# 10M_PPS_OUT.net
KiCad netlist of a schematic drawn in Altium Designer
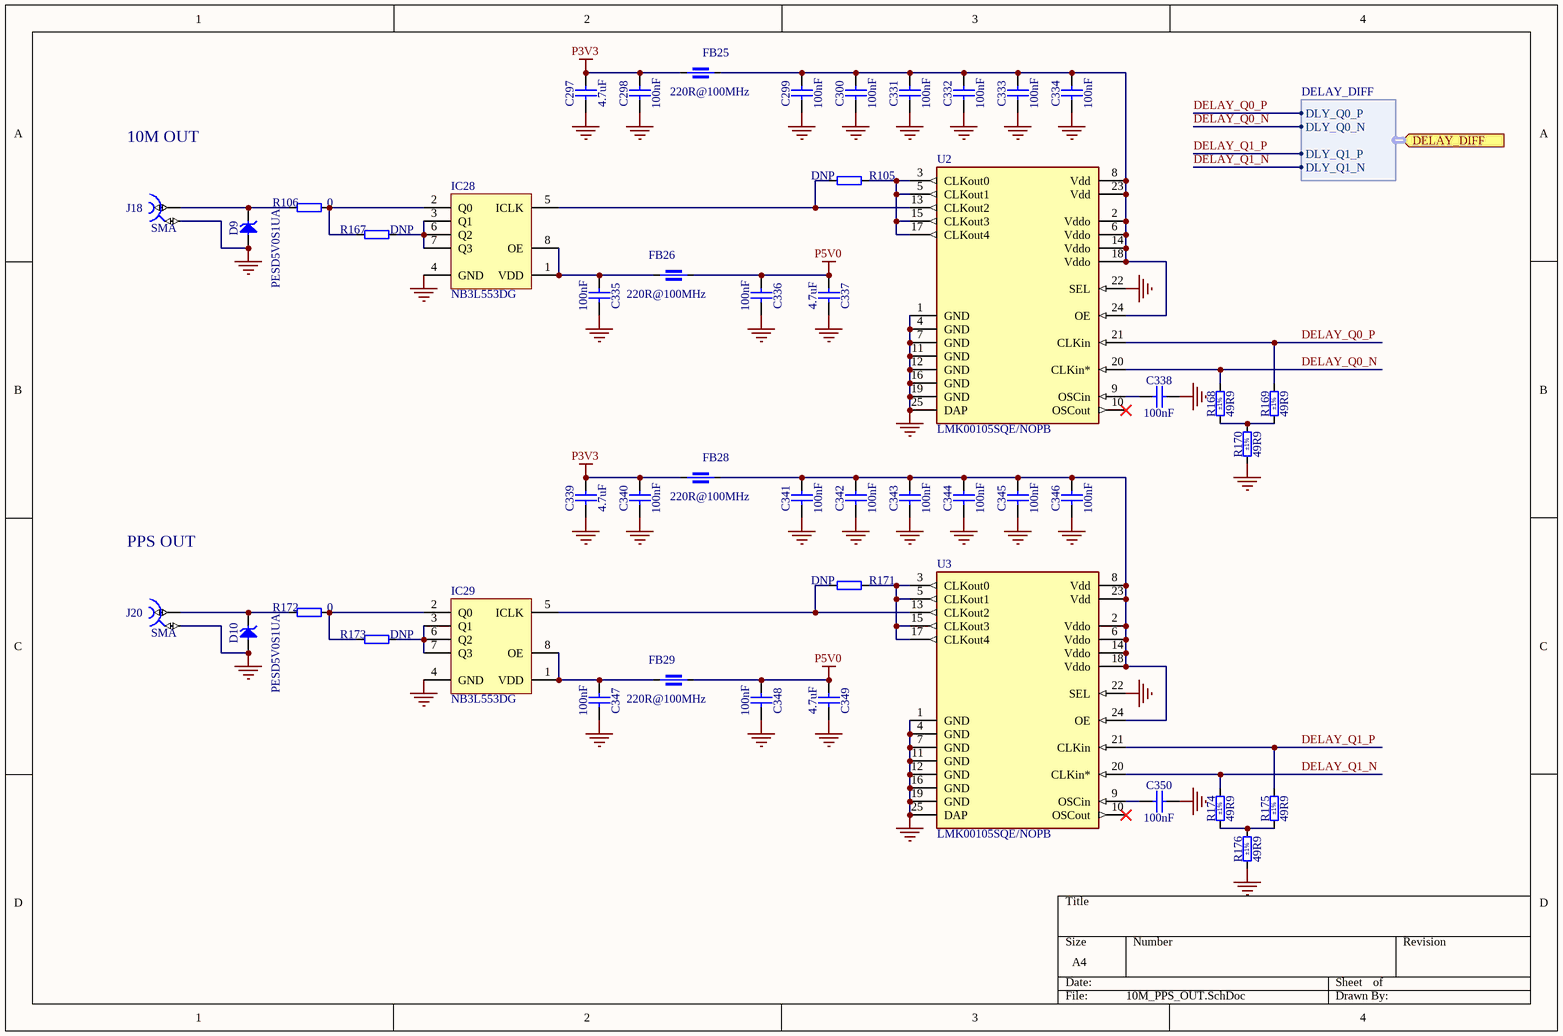
[diagram p0: 10M_PPS_OUT.SchDoc]

(export (version "E")
  (design (tool "Eeschema 10.0.6"))
  (components
    (comp (ref "C297")
      (value "4.7uF")
      (footprint "CAPC1005X55N")
      (description "Non-polarised capacitor")
      (fields
        (field (name "PART NUMBER") "CC0402_4.7UF_6.3V_20%_X5R")
        (field (name "VOLTAGE") "6.3V")
        (field (name "AUTHOR") "CERN DEM JLC")
      )
      (libsource (lib "Capacitors") (part "Capacitor - non polarized"))
    )
    (comp (ref "C298")
      (value "100nF")
      (footprint "CAPC0603X33N")
      (description "Non-polarised capacitor")
      (fields
        (field (name "PART NUMBER") "CC0201_100NF_6.3V_10%_X5R")
        (field (name "VOLTAGE") "6.3V")
        (field (name "AUTHOR") "CERN DEM JLC")
      )
      (libsource (lib "Capacitors") (part "Capacitor - non polarized"))
    )
    (comp (ref "C299")
      (value "100nF")
      (footprint "CAPC0603X33N")
      (description "Non-polarised capacitor")
      (fields
        (field (name "PART NUMBER") "CC0201_100NF_6.3V_10%_X5R")
        (field (name "VOLTAGE") "6.3V")
        (field (name "AUTHOR") "CERN DEM JLC")
      )
      (libsource (lib "Capacitors") (part "Capacitor - non polarized"))
    )
    (comp (ref "C300")
      (value "100nF")
      (footprint "CAPC0603X33N")
      (description "Non-polarised capacitor")
      (fields
        (field (name "PART NUMBER") "CC0201_100NF_6.3V_10%_X5R")
        (field (name "VOLTAGE") "6.3V")
        (field (name "AUTHOR") "CERN DEM JLC")
      )
      (libsource (lib "Capacitors") (part "Capacitor - non polarized"))
    )
    (comp (ref "C331")
      (value "100nF")
      (footprint "CAPC0603X33N")
      (description "Non-polarised capacitor")
      (fields
        (field (name "PART NUMBER") "CC0201_100NF_6.3V_10%_X5R")
        (field (name "VOLTAGE") "6.3V")
        (field (name "AUTHOR") "CERN DEM JLC")
      )
      (libsource (lib "Capacitors") (part "Capacitor - non polarized"))
    )
    (comp (ref "C332")
      (value "100nF")
      (footprint "CAPC0603X33N")
      (description "Non-polarised capacitor")
      (fields
        (field (name "PART NUMBER") "CC0201_100NF_6.3V_10%_X5R")
        (field (name "VOLTAGE") "6.3V")
        (field (name "AUTHOR") "CERN DEM JLC")
      )
      (libsource (lib "Capacitors") (part "Capacitor - non polarized"))
    )
    (comp (ref "C333")
      (value "100nF")
      (footprint "CAPC0603X33N")
      (description "Non-polarised capacitor")
      (fields
        (field (name "PART NUMBER") "CC0201_100NF_6.3V_10%_X5R")
        (field (name "VOLTAGE") "6.3V")
        (field (name "AUTHOR") "CERN DEM JLC")
      )
      (libsource (lib "Capacitors") (part "Capacitor - non polarized"))
    )
    (comp (ref "C334")
      (value "100nF")
      (footprint "CAPC0603X33N")
      (description "Non-polarised capacitor")
      (fields
        (field (name "PART NUMBER") "CC0201_100NF_6.3V_10%_X5R")
        (field (name "VOLTAGE") "6.3V")
        (field (name "AUTHOR") "CERN DEM JLC")
      )
      (libsource (lib "Capacitors") (part "Capacitor - non polarized"))
    )
    (comp (ref "C335")
      (value "100nF")
      (footprint "CAPC0603X33N")
      (description "Non-polarised capacitor")
      (fields
        (field (name "PART NUMBER") "CC0201_100NF_6.3V_10%_X5R")
        (field (name "VOLTAGE") "6.3V")
        (field (name "AUTHOR") "CERN DEM JLC")
      )
      (libsource (lib "Capacitors") (part "Capacitor - non polarized"))
    )
    (comp (ref "C336")
      (value "100nF")
      (footprint "CAPC0603X33N")
      (description "Non-polarised capacitor")
      (fields
        (field (name "PART NUMBER") "CC0201_100NF_6.3V_10%_X5R")
        (field (name "VOLTAGE") "6.3V")
        (field (name "AUTHOR") "CERN DEM JLC")
      )
      (libsource (lib "Capacitors") (part "Capacitor - non polarized"))
    )
    (comp (ref "C337")
      (value "4.7uF")
      (footprint "CAPC1005X55N")
      (description "Non-polarised capacitor")
      (fields
        (field (name "PART NUMBER") "CC0402_4.7UF_6.3V_20%_X5R")
        (field (name "VOLTAGE") "6.3V")
        (field (name "AUTHOR") "CERN DEM JLC")
      )
      (libsource (lib "Capacitors") (part "Capacitor - non polarized"))
    )
    (comp (ref "C338")
      (value "100nF")
      (footprint "CAPC0603X33N")
      (description "Non-polarised capacitor")
      (fields
        (field (name "PART NUMBER") "CC0201_100NF_6.3V_10%_X5R")
        (field (name "VOLTAGE") "6.3V")
        (field (name "AUTHOR") "CERN DEM JLC")
      )
      (libsource (lib "Capacitors") (part "Capacitor - non polarized"))
    )
    (comp (ref "C339")
      (value "4.7uF")
      (footprint "CAPC1005X55N")
      (description "Non-polarised capacitor")
      (fields
        (field (name "PART NUMBER") "CC0402_4.7UF_6.3V_20%_X5R")
        (field (name "VOLTAGE") "6.3V")
        (field (name "AUTHOR") "CERN DEM JLC")
      )
      (libsource (lib "Capacitors") (part "Capacitor - non polarized"))
    )
    (comp (ref "C340")
      (value "100nF")
      (footprint "CAPC0603X33N")
      (description "Non-polarised capacitor")
      (fields
        (field (name "PART NUMBER") "CC0201_100NF_6.3V_10%_X5R")
        (field (name "VOLTAGE") "6.3V")
        (field (name "AUTHOR") "CERN DEM JLC")
      )
      (libsource (lib "Capacitors") (part "Capacitor - non polarized"))
    )
    (comp (ref "C341")
      (value "100nF")
      (footprint "CAPC0603X33N")
      (description "Non-polarised capacitor")
      (fields
        (field (name "PART NUMBER") "CC0201_100NF_6.3V_10%_X5R")
        (field (name "VOLTAGE") "6.3V")
        (field (name "AUTHOR") "CERN DEM JLC")
      )
      (libsource (lib "Capacitors") (part "Capacitor - non polarized"))
    )
    (comp (ref "C342")
      (value "100nF")
      (footprint "CAPC0603X33N")
      (description "Non-polarised capacitor")
      (fields
        (field (name "PART NUMBER") "CC0201_100NF_6.3V_10%_X5R")
        (field (name "VOLTAGE") "6.3V")
        (field (name "AUTHOR") "CERN DEM JLC")
      )
      (libsource (lib "Capacitors") (part "Capacitor - non polarized"))
    )
    (comp (ref "C343")
      (value "100nF")
      (footprint "CAPC0603X33N")
      (description "Non-polarised capacitor")
      (fields
        (field (name "PART NUMBER") "CC0201_100NF_6.3V_10%_X5R")
        (field (name "VOLTAGE") "6.3V")
        (field (name "AUTHOR") "CERN DEM JLC")
      )
      (libsource (lib "Capacitors") (part "Capacitor - non polarized"))
    )
    (comp (ref "C344")
      (value "100nF")
      (footprint "CAPC0603X33N")
      (description "Non-polarised capacitor")
      (fields
        (field (name "PART NUMBER") "CC0201_100NF_6.3V_10%_X5R")
        (field (name "VOLTAGE") "6.3V")
        (field (name "AUTHOR") "CERN DEM JLC")
      )
      (libsource (lib "Capacitors") (part "Capacitor - non polarized"))
    )
    (comp (ref "C345")
      (value "100nF")
      (footprint "CAPC0603X33N")
      (description "Non-polarised capacitor")
      (fields
        (field (name "PART NUMBER") "CC0201_100NF_6.3V_10%_X5R")
        (field (name "VOLTAGE") "6.3V")
        (field (name "AUTHOR") "CERN DEM JLC")
      )
      (libsource (lib "Capacitors") (part "Capacitor - non polarized"))
    )
    (comp (ref "C346")
      (value "100nF")
      (footprint "CAPC0603X33N")
      (description "Non-polarised capacitor")
      (fields
        (field (name "PART NUMBER") "CC0201_100NF_6.3V_10%_X5R")
        (field (name "VOLTAGE") "6.3V")
        (field (name "AUTHOR") "CERN DEM JLC")
      )
      (libsource (lib "Capacitors") (part "Capacitor - non polarized"))
    )
    (comp (ref "C347")
      (value "100nF")
      (footprint "CAPC0603X33N")
      (description "Non-polarised capacitor")
      (fields
        (field (name "PART NUMBER") "CC0201_100NF_6.3V_10%_X5R")
        (field (name "VOLTAGE") "6.3V")
        (field (name "AUTHOR") "CERN DEM JLC")
      )
      (libsource (lib "Capacitors") (part "Capacitor - non polarized"))
    )
    (comp (ref "C348")
      (value "100nF")
      (footprint "CAPC0603X33N")
      (description "Non-polarised capacitor")
      (fields
        (field (name "PART NUMBER") "CC0201_100NF_6.3V_10%_X5R")
        (field (name "VOLTAGE") "6.3V")
        (field (name "AUTHOR") "CERN DEM JLC")
      )
      (libsource (lib "Capacitors") (part "Capacitor - non polarized"))
    )
    (comp (ref "C349")
      (value "4.7uF")
      (footprint "CAPC1005X55N")
      (description "Non-polarised capacitor")
      (fields
        (field (name "PART NUMBER") "CC0402_4.7UF_6.3V_20%_X5R")
        (field (name "VOLTAGE") "6.3V")
        (field (name "AUTHOR") "CERN DEM JLC")
      )
      (libsource (lib "Capacitors") (part "Capacitor - non polarized"))
    )
    (comp (ref "C350")
      (value "100nF")
      (footprint "CAPC0603X33N")
      (description "Non-polarised capacitor")
      (fields
        (field (name "PART NUMBER") "CC0201_100NF_6.3V_10%_X5R")
        (field (name "VOLTAGE") "6.3V")
        (field (name "AUTHOR") "CERN DEM JLC")
      )
      (libsource (lib "Capacitors") (part "Capacitor - non polarized"))
    )
    (comp (ref "D9")
      (value "PESD5V0S1UA")
      (footprint "SOD2512X110N")
      (description "Transient Voltage Suppressor Diode (Uni-Directional)")
      (fields
        (field (name "VOLTAGE") "5V")
        (field (name "POWER") "890W")
        (field (name "AUTHOR") "CERN DEM JLC")
      )
      (libsource (lib "ICs And Semiconductors") (part "Diode TVS Uni-Directional"))
    )
    (comp (ref "D10")
      (value "PESD5V0S1UA")
      (footprint "SOD2512X110N")
      (description "Transient Voltage Suppressor Diode (Uni-Directional)")
      (fields
        (field (name "VOLTAGE") "5V")
        (field (name "POWER") "890W")
        (field (name "AUTHOR") "CERN DEM JLC")
      )
      (libsource (lib "ICs And Semiconductors") (part "Diode TVS Uni-Directional"))
    )
    (comp (ref "FB25")
      (value "220R@100MHz")
      (footprint "INDC1608X95N")
      (fields
        (field (name "TOLERANCE") "±25%")
        (field (name "PART NUMBER") "IND0603_MURATA_BLM18SG221TN1")
        (field (name "POWER") "2.5A")
        (field (name "AUTHOR") "CERN DEM MR")
      )
      (libsource (lib "Inductors & Transformers") (part "Ferrite Bead"))
    )
    (comp (ref "FB26")
      (value "220R@100MHz")
      (footprint "INDC1608X95N")
      (fields
        (field (name "TOLERANCE") "±25%")
        (field (name "PART NUMBER") "IND0603_MURATA_BLM18SG221TN1")
        (field (name "POWER") "2.5A")
        (field (name "AUTHOR") "CERN DEM MR")
      )
      (libsource (lib "") (part "Ferrite Bead_1"))
    )
    (comp (ref "FB28")
      (value "220R@100MHz")
      (footprint "INDC1608X95N")
      (fields
        (field (name "TOLERANCE") "±25%")
        (field (name "PART NUMBER") "IND0603_MURATA_BLM18SG221TN1")
        (field (name "POWER") "2.5A")
        (field (name "AUTHOR") "CERN DEM MR")
      )
      (libsource (lib "Inductors & Transformers") (part "Ferrite Bead"))
    )
    (comp (ref "FB29")
      (value "220R@100MHz")
      (footprint "INDC1608X95N")
      (fields
        (field (name "TOLERANCE") "±25%")
        (field (name "PART NUMBER") "IND0603_MURATA_BLM18SG221TN1")
        (field (name "POWER") "2.5A")
        (field (name "AUTHOR") "CERN DEM MR")
      )
      (libsource (lib "") (part "Ferrite Bead_1"))
    )
    (comp (ref "IC28")
      (value "NB3L553DG")
      (footprint "SOIC127P600X175-8N")
      (libsource (lib "MGlib") (part "NB3L553DG"))
    )
    (comp (ref "IC29")
      (value "NB3L553DG")
      (footprint "SOIC127P600X175-8N")
      (libsource (lib "MGlib") (part "NB3L553DG"))
    )
    (comp (ref "J18")
      (value "SMA")
      (footprint "HUBER-SUHNER_85_SMA-50-0-101/111_NE")
      (fields
        (field (name "PART NUMBER") "HUBER-SUHNER_85_SMA-50-0-101/111_NE")
        (field (name "MANUFACTURER") "HUBER+SUHNER")
        (field (name "MANUFACTURER PART NUMBER") "85_SMA-50-0-101/111_NE")
        (field (name "AUTHOR") "CERN DEM JLC")
      )
      (libsource (lib "Connectors") (part "Coax_1Female_1Shield"))
    )
    (comp (ref "J20")
      (value "SMA")
      (footprint "HUBER-SUHNER_85_SMA-50-0-101/111_NE")
      (fields
        (field (name "PART NUMBER") "HUBER-SUHNER_85_SMA-50-0-101/111_NE")
        (field (name "MANUFACTURER") "HUBER+SUHNER")
        (field (name "MANUFACTURER PART NUMBER") "85_SMA-50-0-101/111_NE")
        (field (name "AUTHOR") "CERN DEM JLC")
      )
      (libsource (lib "Connectors") (part "Coax_1Female_1Shield"))
    )
    (comp (ref "R105")
      (value "DNP")
      (footprint "RESC1005X40N")
      (description "Resistor")
      (fields
        (field (name "PART NUMBER") "R0402_0R_JUMPER")
        (field (name "MANUFACTURER") "GENERIC")
        (field (name "AUTHOR") "CERN DEM JLC")
      )
      (libsource (lib "Resistors") (part "Resistor"))
    )
    (comp (ref "R106")
      (value "0")
      (footprint "RESC1005X40N")
      (description "Resistor")
      (fields
        (field (name "PART NUMBER") "R0402_0R_JUMPER")
        (field (name "MANUFACTURER") "GENERIC")
        (field (name "AUTHOR") "CERN DEM JLC")
      )
      (libsource (lib "Resistors") (part "Resistor"))
    )
    (comp (ref "R167")
      (value "DNP")
      (footprint "RESC1005X40N")
      (description "Resistor")
      (fields
        (field (name "PART NUMBER") "R0402_0R_JUMPER")
        (field (name "MANUFACTURER") "GENERIC")
        (field (name "AUTHOR") "CERN DEM JLC")
      )
      (libsource (lib "Resistors") (part "Resistor"))
    )
    (comp (ref "R168")
      (value "49R9")
      (footprint "RESC1005X40N")
      (description "Resistor - 1%")
      (fields
        (field (name "TOLERANCE") "±1%")
        (field (name "PART NUMBER") "R0402_49R9_1%_0.0625W_100PPM")
        (field (name "POWER") "0.0625W")
        (field (name "AUTHOR") "CERN DEM JLC")
      )
      (libsource (lib "Resistors") (part "Resistor - 1%"))
    )
    (comp (ref "R169")
      (value "49R9")
      (footprint "RESC1005X40N")
      (description "Resistor - 1%")
      (fields
        (field (name "TOLERANCE") "±1%")
        (field (name "PART NUMBER") "R0402_49R9_1%_0.0625W_100PPM")
        (field (name "POWER") "0.0625W")
        (field (name "AUTHOR") "CERN DEM JLC")
      )
      (libsource (lib "Resistors") (part "Resistor - 1%"))
    )
    (comp (ref "R170")
      (value "49R9")
      (footprint "RESC1005X40N")
      (description "Resistor - 1%")
      (fields
        (field (name "TOLERANCE") "±1%")
        (field (name "PART NUMBER") "R0402_49R9_1%_0.0625W_100PPM")
        (field (name "POWER") "0.0625W")
        (field (name "AUTHOR") "CERN DEM JLC")
      )
      (libsource (lib "Resistors") (part "Resistor - 1%"))
    )
    (comp (ref "R171")
      (value "DNP")
      (footprint "RESC1005X40N")
      (description "Resistor")
      (fields
        (field (name "PART NUMBER") "R0402_0R_JUMPER")
        (field (name "MANUFACTURER") "GENERIC")
        (field (name "AUTHOR") "CERN DEM JLC")
      )
      (libsource (lib "Resistors") (part "Resistor"))
    )
    (comp (ref "R172")
      (value "0")
      (footprint "RESC1005X40N")
      (description "Resistor")
      (fields
        (field (name "PART NUMBER") "R0402_0R_JUMPER")
        (field (name "MANUFACTURER") "GENERIC")
        (field (name "AUTHOR") "CERN DEM JLC")
      )
      (libsource (lib "Resistors") (part "Resistor"))
    )
    (comp (ref "R173")
      (value "DNP")
      (footprint "RESC1005X40N")
      (description "Resistor")
      (fields
        (field (name "PART NUMBER") "R0402_0R_JUMPER")
        (field (name "MANUFACTURER") "GENERIC")
        (field (name "AUTHOR") "CERN DEM JLC")
      )
      (libsource (lib "Resistors") (part "Resistor"))
    )
    (comp (ref "R174")
      (value "49R9")
      (footprint "RESC1005X40N")
      (description "Resistor - 1%")
      (fields
        (field (name "TOLERANCE") "±1%")
        (field (name "PART NUMBER") "R0402_49R9_1%_0.0625W_100PPM")
        (field (name "POWER") "0.0625W")
        (field (name "AUTHOR") "CERN DEM JLC")
      )
      (libsource (lib "Resistors") (part "Resistor - 1%"))
    )
    (comp (ref "R175")
      (value "49R9")
      (footprint "RESC1005X40N")
      (description "Resistor - 1%")
      (fields
        (field (name "TOLERANCE") "±1%")
        (field (name "PART NUMBER") "R0402_49R9_1%_0.0625W_100PPM")
        (field (name "POWER") "0.0625W")
        (field (name "AUTHOR") "CERN DEM JLC")
      )
      (libsource (lib "Resistors") (part "Resistor - 1%"))
    )
    (comp (ref "R176")
      (value "49R9")
      (footprint "RESC1005X40N")
      (description "Resistor - 1%")
      (fields
        (field (name "TOLERANCE") "±1%")
        (field (name "PART NUMBER") "R0402_49R9_1%_0.0625W_100PPM")
        (field (name "POWER") "0.0625W")
        (field (name "AUTHOR") "CERN DEM JLC")
      )
      (libsource (lib "Resistors") (part "Resistor - 1%"))
    )
    (comp (ref "U2")
      (value "LMK00105SQE/NOPB")
      (footprint "FP-RTW0024A-MFG")
      (description "IC CLK BUFFER 2:5 200MHZ 24WQFN")
      (libsource (lib "Altium Content Vault") (part "44324d68dc54cc7ef1e7b48c7c296ee"))
    )
    (comp (ref "U3")
      (value "LMK00105SQE/NOPB")
      (footprint "FP-RTW0024A-MFG")
      (description "IC CLK BUFFER 2:5 200MHZ 24WQFN")
      (libsource (lib "Altium Content Vault") (part "44324d68dc54cc7ef1e7b48c7c296ee"))
    )
  )
  (nets
    (net (code "2") (name "/DELAY_Q0_N") (class "Default")
      (node (ref "R168") (pin "2") (pinfunction "2_2") (pintype "passive"))
      (node (ref "U2") (pin "20") (pinfunction "CLKin*_20") (pintype "input"))
    )
    (net (code "3") (name "/DELAY_Q0_P") (class "Default")
      (node (ref "R169") (pin "2") (pinfunction "2_2") (pintype "passive"))
      (node (ref "U2") (pin "21") (pinfunction "CLKin_21") (pintype "input"))
    )
    (net (code "4") (name "/DELAY_Q1_N") (class "Default")
      (node (ref "R174") (pin "2") (pinfunction "2_2") (pintype "passive"))
      (node (ref "U3") (pin "20") (pinfunction "CLKin*_20") (pintype "input"))
    )
    (net (code "5") (name "/DELAY_Q1_P") (class "Default")
      (node (ref "R175") (pin "2") (pinfunction "2_2") (pintype "passive"))
      (node (ref "U3") (pin "21") (pinfunction "CLKin_21") (pintype "input"))
    )
    (net (code "7") (name "GND") (class "Default")
      (node (ref "C297") (pin "1") (pinfunction "1_1") (pintype "passive"))
      (node (ref "C298") (pin "1") (pinfunction "1_1") (pintype "passive"))
      (node (ref "C299") (pin "1") (pinfunction "1_1") (pintype "passive"))
      (node (ref "C300") (pin "1") (pinfunction "1_1") (pintype "passive"))
      (node (ref "C331") (pin "1") (pinfunction "1_1") (pintype "passive"))
      (node (ref "C332") (pin "1") (pinfunction "1_1") (pintype "passive"))
      (node (ref "C333") (pin "1") (pinfunction "1_1") (pintype "passive"))
      (node (ref "C334") (pin "1") (pinfunction "1_1") (pintype "passive"))
      (node (ref "C335") (pin "1") (pinfunction "1_1") (pintype "passive"))
      (node (ref "C336") (pin "1") (pinfunction "1_1") (pintype "passive"))
      (node (ref "C337") (pin "1") (pinfunction "1_1") (pintype "passive"))
      (node (ref "C338") (pin "2") (pinfunction "2_2") (pintype "passive"))
      (node (ref "C339") (pin "1") (pinfunction "1_1") (pintype "passive"))
      (node (ref "C340") (pin "1") (pinfunction "1_1") (pintype "passive"))
      (node (ref "C341") (pin "1") (pinfunction "1_1") (pintype "passive"))
      (node (ref "C342") (pin "1") (pinfunction "1_1") (pintype "passive"))
      (node (ref "C343") (pin "1") (pinfunction "1_1") (pintype "passive"))
      (node (ref "C344") (pin "1") (pinfunction "1_1") (pintype "passive"))
      (node (ref "C345") (pin "1") (pinfunction "1_1") (pintype "passive"))
      (node (ref "C346") (pin "1") (pinfunction "1_1") (pintype "passive"))
      (node (ref "C347") (pin "1") (pinfunction "1_1") (pintype "passive"))
      (node (ref "C348") (pin "1") (pinfunction "1_1") (pintype "passive"))
      (node (ref "C349") (pin "1") (pinfunction "1_1") (pintype "passive"))
      (node (ref "C350") (pin "2") (pinfunction "2_2") (pintype "passive"))
      (node (ref "D10") (pin "2") (pinfunction "A_2") (pintype "passive"))
      (node (ref "D9") (pin "2") (pinfunction "A_2") (pintype "passive"))
      (node (ref "IC28") (pin "4") (pinfunction "GND_4") (pintype "passive"))
      (node (ref "IC29") (pin "4") (pinfunction "GND_4") (pintype "passive"))
      (node (ref "J18") (pin "2") (pinfunction "2_2") (pintype "bidirectional"))
      (node (ref "J20") (pin "2") (pinfunction "2_2") (pintype "bidirectional"))
      (node (ref "R170") (pin "1") (pinfunction "1_1") (pintype "passive"))
      (node (ref "R176") (pin "1") (pinfunction "1_1") (pintype "passive"))
      (node (ref "U2") (pin "1") (pinfunction "GND_1") (pintype "power_in"))
      (node (ref "U2") (pin "11") (pinfunction "GND_11") (pintype "power_in"))
      (node (ref "U2") (pin "12") (pinfunction "GND_12") (pintype "power_in"))
      (node (ref "U2") (pin "16") (pinfunction "GND_16") (pintype "power_in"))
      (node (ref "U2") (pin "19") (pinfunction "GND_19") (pintype "power_in"))
      (node (ref "U2") (pin "22") (pinfunction "SEL_22") (pintype "input"))
      (node (ref "U2") (pin "25") (pinfunction "DAP_25") (pintype "passive"))
      (node (ref "U2") (pin "4") (pinfunction "GND_4") (pintype "power_in"))
      (node (ref "U2") (pin "7") (pinfunction "GND_7") (pintype "power_in"))
      (node (ref "U3") (pin "1") (pinfunction "GND_1") (pintype "power_in"))
      (node (ref "U3") (pin "11") (pinfunction "GND_11") (pintype "power_in"))
      (node (ref "U3") (pin "12") (pinfunction "GND_12") (pintype "power_in"))
      (node (ref "U3") (pin "16") (pinfunction "GND_16") (pintype "power_in"))
      (node (ref "U3") (pin "19") (pinfunction "GND_19") (pintype "power_in"))
      (node (ref "U3") (pin "22") (pinfunction "SEL_22") (pintype "input"))
      (node (ref "U3") (pin "25") (pinfunction "DAP_25") (pintype "passive"))
      (node (ref "U3") (pin "4") (pinfunction "GND_4") (pintype "power_in"))
      (node (ref "U3") (pin "7") (pinfunction "GND_7") (pintype "power_in"))
    )
    (net (code "8") (name "Net-(D9-C)") (class "Default")
      (node (ref "D9") (pin "1") (pinfunction "C_1") (pintype "passive"))
      (node (ref "J18") (pin "1") (pinfunction "1_1") (pintype "bidirectional"))
      (node (ref "R106") (pin "1") (pinfunction "1_1") (pintype "passive"))
    )
    (net (code "9") (name "Net-(D10-C)") (class "Default")
      (node (ref "D10") (pin "1") (pinfunction "C_1") (pintype "passive"))
      (node (ref "J20") (pin "1") (pinfunction "1_1") (pintype "bidirectional"))
      (node (ref "R172") (pin "1") (pinfunction "1_1") (pintype "passive"))
    )
    (net (code "10") (name "Net-(IC28-ICLK)") (class "Default")
      (node (ref "IC28") (pin "5") (pinfunction "ICLK_5") (pintype "passive"))
      (node (ref "R105") (pin "2") (pinfunction "2_2") (pintype "passive"))
      (node (ref "U2") (pin "13") (pinfunction "CLKout2_13") (pintype "output"))
    )
    (net (code "11") (name "Net-(IC28-OE)") (class "Default")
      (node (ref "C335") (pin "2") (pinfunction "2_2") (pintype "passive"))
      (node (ref "FB26") (pin "2") (pinfunction "2_2") (pintype "passive"))
      (node (ref "IC28") (pin "1") (pinfunction "VDD_1") (pintype "passive"))
      (node (ref "IC28") (pin "8") (pinfunction "OE_8") (pintype "passive"))
    )
    (net (code "12") (name "Net-(IC28-Q0)") (class "Default")
      (node (ref "IC28") (pin "2") (pinfunction "Q0_2") (pintype "passive"))
      (node (ref "R106") (pin "2") (pinfunction "2_2") (pintype "passive"))
      (node (ref "R167") (pin "1") (pinfunction "1_1") (pintype "passive"))
    )
    (net (code "13") (name "Net-(IC28-Q1)") (class "Default")
      (node (ref "IC28") (pin "3") (pinfunction "Q1_3") (pintype "passive"))
      (node (ref "IC28") (pin "6") (pinfunction "Q2_6") (pintype "passive"))
      (node (ref "IC28") (pin "7") (pinfunction "Q3_7") (pintype "passive"))
      (node (ref "R167") (pin "2") (pinfunction "2_2") (pintype "passive"))
    )
    (net (code "14") (name "Net-(IC29-ICLK)") (class "Default")
      (node (ref "IC29") (pin "5") (pinfunction "ICLK_5") (pintype "passive"))
      (node (ref "R171") (pin "2") (pinfunction "2_2") (pintype "passive"))
      (node (ref "U3") (pin "13") (pinfunction "CLKout2_13") (pintype "output"))
    )
    (net (code "15") (name "Net-(IC29-OE)") (class "Default")
      (node (ref "C347") (pin "2") (pinfunction "2_2") (pintype "passive"))
      (node (ref "FB29") (pin "2") (pinfunction "2_2") (pintype "passive"))
      (node (ref "IC29") (pin "1") (pinfunction "VDD_1") (pintype "passive"))
      (node (ref "IC29") (pin "8") (pinfunction "OE_8") (pintype "passive"))
    )
    (net (code "16") (name "Net-(IC29-Q0)") (class "Default")
      (node (ref "IC29") (pin "2") (pinfunction "Q0_2") (pintype "passive"))
      (node (ref "R172") (pin "2") (pinfunction "2_2") (pintype "passive"))
      (node (ref "R173") (pin "1") (pinfunction "1_1") (pintype "passive"))
    )
    (net (code "17") (name "Net-(IC29-Q1)") (class "Default")
      (node (ref "IC29") (pin "3") (pinfunction "Q1_3") (pintype "passive"))
      (node (ref "IC29") (pin "6") (pinfunction "Q2_6") (pintype "passive"))
      (node (ref "IC29") (pin "7") (pinfunction "Q3_7") (pintype "passive"))
      (node (ref "R173") (pin "2") (pinfunction "2_2") (pintype "passive"))
    )
    (net (code "18") (name "Net-(R168-Pad1)") (class "Default")
      (node (ref "R168") (pin "1") (pinfunction "1_1") (pintype "passive"))
      (node (ref "R169") (pin "1") (pinfunction "1_1") (pintype "passive"))
      (node (ref "R170") (pin "2") (pinfunction "2_2") (pintype "passive"))
    )
    (net (code "19") (name "Net-(R174-Pad1)") (class "Default")
      (node (ref "R174") (pin "1") (pinfunction "1_1") (pintype "passive"))
      (node (ref "R175") (pin "1") (pinfunction "1_1") (pintype "passive"))
      (node (ref "R176") (pin "2") (pinfunction "2_2") (pintype "passive"))
    )
    (net (code "20") (name "Net-(U2-CLKout0)") (class "Default")
      (node (ref "R105") (pin "1") (pinfunction "1_1") (pintype "passive"))
      (node (ref "U2") (pin "15") (pinfunction "CLKout3_15") (pintype "output"))
      (node (ref "U2") (pin "17") (pinfunction "CLKout4_17") (pintype "output"))
      (node (ref "U2") (pin "3") (pinfunction "CLKout0_3") (pintype "output"))
      (node (ref "U2") (pin "5") (pinfunction "CLKout1_5") (pintype "output"))
    )
    (net (code "21") (name "Net-(U2-OE)") (class "Default")
      (node (ref "C299") (pin "2") (pinfunction "2_2") (pintype "passive"))
      (node (ref "C300") (pin "2") (pinfunction "2_2") (pintype "passive"))
      (node (ref "C331") (pin "2") (pinfunction "2_2") (pintype "passive"))
      (node (ref "C332") (pin "2") (pinfunction "2_2") (pintype "passive"))
      (node (ref "C333") (pin "2") (pinfunction "2_2") (pintype "passive"))
      (node (ref "C334") (pin "2") (pinfunction "2_2") (pintype "passive"))
      (node (ref "FB25") (pin "2") (pinfunction "2_2") (pintype "passive"))
      (node (ref "U2") (pin "14") (pinfunction "Vddo_14") (pintype "power_in"))
      (node (ref "U2") (pin "18") (pinfunction "Vddo_18") (pintype "power_in"))
      (node (ref "U2") (pin "2") (pinfunction "Vddo_2") (pintype "power_in"))
      (node (ref "U2") (pin "23") (pinfunction "Vdd_23") (pintype "power_in"))
      (node (ref "U2") (pin "24") (pinfunction "OE_24") (pintype "input"))
      (node (ref "U2") (pin "6") (pinfunction "Vddo_6") (pintype "power_in"))
      (node (ref "U2") (pin "8") (pinfunction "Vdd_8") (pintype "power_in"))
    )
    (net (code "22") (name "Net-(U2-OSCin)") (class "Default")
      (node (ref "C338") (pin "1") (pinfunction "1_1") (pintype "passive"))
      (node (ref "U2") (pin "9") (pinfunction "OSCin_9") (pintype "input"))
    )
    (net (code "23") (name "Net-(U3-CLKout0)") (class "Default")
      (node (ref "R171") (pin "1") (pinfunction "1_1") (pintype "passive"))
      (node (ref "U3") (pin "15") (pinfunction "CLKout3_15") (pintype "output"))
      (node (ref "U3") (pin "17") (pinfunction "CLKout4_17") (pintype "output"))
      (node (ref "U3") (pin "3") (pinfunction "CLKout0_3") (pintype "output"))
      (node (ref "U3") (pin "5") (pinfunction "CLKout1_5") (pintype "output"))
    )
    (net (code "24") (name "Net-(U3-OE)") (class "Default")
      (node (ref "C341") (pin "2") (pinfunction "2_2") (pintype "passive"))
      (node (ref "C342") (pin "2") (pinfunction "2_2") (pintype "passive"))
      (node (ref "C343") (pin "2") (pinfunction "2_2") (pintype "passive"))
      (node (ref "C344") (pin "2") (pinfunction "2_2") (pintype "passive"))
      (node (ref "C345") (pin "2") (pinfunction "2_2") (pintype "passive"))
      (node (ref "C346") (pin "2") (pinfunction "2_2") (pintype "passive"))
      (node (ref "FB28") (pin "2") (pinfunction "2_2") (pintype "passive"))
      (node (ref "U3") (pin "14") (pinfunction "Vddo_14") (pintype "power_in"))
      (node (ref "U3") (pin "18") (pinfunction "Vddo_18") (pintype "power_in"))
      (node (ref "U3") (pin "2") (pinfunction "Vddo_2") (pintype "power_in"))
      (node (ref "U3") (pin "23") (pinfunction "Vdd_23") (pintype "power_in"))
      (node (ref "U3") (pin "24") (pinfunction "OE_24") (pintype "input"))
      (node (ref "U3") (pin "6") (pinfunction "Vddo_6") (pintype "power_in"))
      (node (ref "U3") (pin "8") (pinfunction "Vdd_8") (pintype "power_in"))
    )
    (net (code "25") (name "Net-(U3-OSCin)") (class "Default")
      (node (ref "C350") (pin "1") (pinfunction "1_1") (pintype "passive"))
      (node (ref "U3") (pin "9") (pinfunction "OSCin_9") (pintype "input"))
    )
    (net (code "26") (name "P3V3") (class "Default")
      (node (ref "C297") (pin "2") (pinfunction "2_2") (pintype "passive"))
      (node (ref "C298") (pin "2") (pinfunction "2_2") (pintype "passive"))
      (node (ref "C339") (pin "2") (pinfunction "2_2") (pintype "passive"))
      (node (ref "C340") (pin "2") (pinfunction "2_2") (pintype "passive"))
      (node (ref "FB25") (pin "1") (pinfunction "1_1") (pintype "passive"))
      (node (ref "FB28") (pin "1") (pinfunction "1_1") (pintype "passive"))
    )
    (net (code "27") (name "P5V0") (class "Default")
      (node (ref "C336") (pin "2") (pinfunction "2_2") (pintype "passive"))
      (node (ref "C337") (pin "2") (pinfunction "2_2") (pintype "passive"))
      (node (ref "C348") (pin "2") (pinfunction "2_2") (pintype "passive"))
      (node (ref "C349") (pin "2") (pinfunction "2_2") (pintype "passive"))
      (node (ref "FB26") (pin "1") (pinfunction "1_1") (pintype "passive"))
      (node (ref "FB29") (pin "1") (pinfunction "1_1") (pintype "passive"))
    )
    (net (code "28") (name "unconnected-(U2-OSCout-Pad10)") (class "Default")
      (node (ref "U2") (pin "10") (pinfunction "OSCout_10") (pintype "output+no_connect"))
    )
    (net (code "29") (name "unconnected-(U3-OSCout-Pad10)") (class "Default")
      (node (ref "U3") (pin "10") (pinfunction "OSCout_10") (pintype "output+no_connect"))
    )
  )
)
